# shm.net
KiCad netlist of a schematic drawn in EAGLE
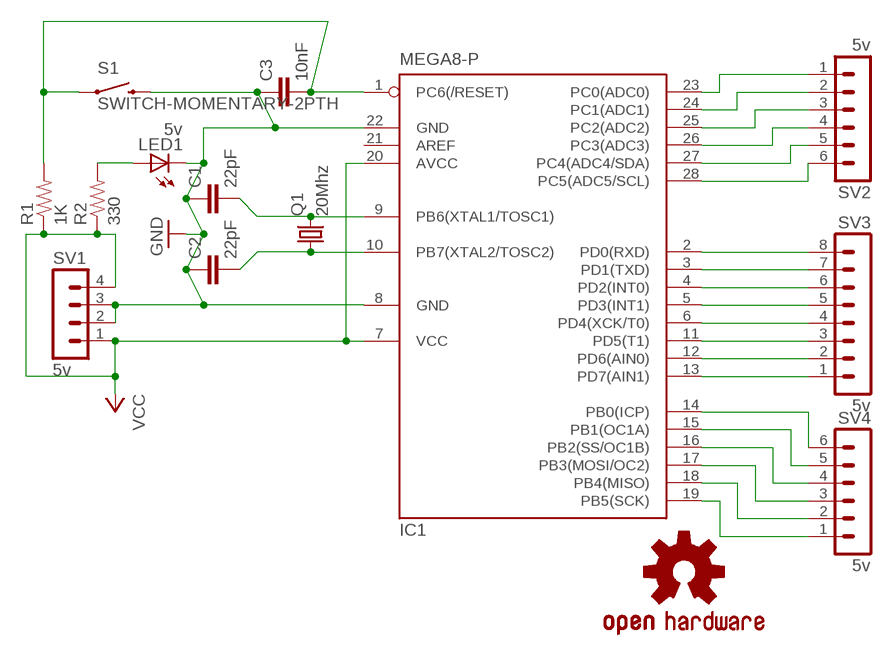
[diagram p0: schematic, sheet 1]

(export (version "E")
  (design (tool "Eeschema 10.0.6"))
  (components
    (comp (ref "C1")
      (value "22pF")
      (footprint "eagle-import:0805")
      (libsource (lib "eagle-import") (part "CAP0805"))
    )
    (comp (ref "C2")
      (value "22pF")
      (footprint "eagle-import:0805")
      (libsource (lib "eagle-import") (part "CAP0805"))
    )
    (comp (ref "C3")
      (value "10nF")
      (footprint "eagle-import:0805")
      (libsource (lib "eagle-import") (part "CAP0805"))
    )
    (comp (ref "IC1")
      (value "MEGA8-P")
      (footprint "eagle-import:DIL28-3")
      (libsource (lib "eagle-import") (part "MEGA8-P"))
    )
    (comp (ref "LED1")
      (value "5v")
      (footprint "eagle-import:CHIPLED_0805")
      (libsource (lib "eagle-import") (part "LEDCHIPLED_0805"))
    )
    (comp (ref "LOGO1")
      (value "OSHW-LOGOL")
      (footprint "eagle-import:OSHW-LOGO-L")
      (libsource (lib "eagle-import") (part "OSHW-LOGOL"))
    )
    (comp (ref "Q1")
      (value "20Mhz")
      (footprint "eagle-import:SM49")
      (libsource (lib "eagle-import") (part "CRYSTALSM49"))
    )
    (comp (ref "R1")
      (value "1K")
      (footprint "eagle-import:0805")
      (libsource (lib "eagle-import") (part "RESISTOR0805-RES"))
    )
    (comp (ref "R2")
      (value "330")
      (footprint "eagle-import:0805")
      (libsource (lib "eagle-import") (part "RESISTOR0805-RES"))
    )
    (comp (ref "S1")
      (value "SWITCH-MOMENTARY-2PTH")
      (footprint "eagle-import:TACTILE-PTH")
      (libsource (lib "eagle-import") (part "SWITCH-MOMENTARY-2PTH"))
    )
    (comp (ref "SV1")
      (value "5v")
      (footprint "eagle-import:MA04-1")
      (libsource (lib "eagle-import") (part "MA04-1"))
    )
    (comp (ref "SV2")
      (value "5v")
      (footprint "eagle-import:MA06-1")
      (libsource (lib "eagle-import") (part "MA06-1"))
    )
    (comp (ref "SV3")
      (value "5v")
      (footprint "eagle-import:MA08-1")
      (libsource (lib "eagle-import") (part "MA08-1"))
    )
    (comp (ref "SV4")
      (value "5v")
      (footprint "eagle-import:MA06-1")
      (libsource (lib "eagle-import") (part "MA06-1"))
    )
  )
  (nets
    (net (code "1") (name "GND") (class "Default")
      (node (ref "C1") (pin "1") (pinfunction "1_1") (pintype "passive"))
      (node (ref "C2") (pin "1") (pinfunction "1_1") (pintype "passive"))
      (node (ref "C3") (pin "1") (pinfunction "1_1") (pintype "passive"))
      (node (ref "IC1") (pin "22") (pinfunction "GND_22") (pintype "power_in"))
      (node (ref "IC1") (pin "8") (pinfunction "GND_8") (pintype "power_in"))
      (node (ref "LED1") (pin "C") (pinfunction "C_C") (pintype "passive"))
      (node (ref "S1") (pin "3") (pinfunction "2_3") (pintype "passive"))
      (node (ref "SV1") (pin "2") (pinfunction "2_2") (pintype "passive"))
      (node (ref "SV1") (pin "3") (pinfunction "3_3") (pintype "passive"))
    )
    (net (code "2") (name "Net-(IC1-PB0(ICP))") (class "Default")
      (node (ref "IC1") (pin "14") (pinfunction "PB0(ICP)_14") (pintype "bidirectional"))
      (node (ref "SV4") (pin "6") (pinfunction "6_6") (pintype "passive"))
    )
    (net (code "3") (name "Net-(IC1-PB1(OC1A))") (class "Default")
      (node (ref "IC1") (pin "15") (pinfunction "PB1(OC1A)_15") (pintype "bidirectional"))
      (node (ref "SV4") (pin "5") (pinfunction "5_5") (pintype "passive"))
    )
    (net (code "4") (name "Net-(IC1-PB2(SS{slash}OC1B))") (class "Default")
      (node (ref "IC1") (pin "16") (pinfunction "PB2(SS/OC1B)_16") (pintype "bidirectional"))
      (node (ref "SV4") (pin "4") (pinfunction "4_4") (pintype "passive"))
    )
    (net (code "5") (name "Net-(IC1-PB3(MOSI{slash}OC2))") (class "Default")
      (node (ref "IC1") (pin "17") (pinfunction "PB3(MOSI/OC2)_17") (pintype "bidirectional"))
      (node (ref "SV4") (pin "3") (pinfunction "3_3") (pintype "passive"))
    )
    (net (code "6") (name "Net-(IC1-PB4(MISO))") (class "Default")
      (node (ref "IC1") (pin "18") (pinfunction "PB4(MISO)_18") (pintype "bidirectional"))
      (node (ref "SV4") (pin "2") (pinfunction "2_2") (pintype "passive"))
    )
    (net (code "7") (name "Net-(IC1-PB5(SCK))") (class "Default")
      (node (ref "IC1") (pin "19") (pinfunction "PB5(SCK)_19") (pintype "bidirectional"))
      (node (ref "SV4") (pin "1") (pinfunction "1_1") (pintype "passive"))
    )
    (net (code "8") (name "Net-(IC1-PB6(XTAL1{slash}TOSC1))") (class "Default")
      (node (ref "C1") (pin "2") (pinfunction "2_2") (pintype "passive"))
      (node (ref "IC1") (pin "9") (pinfunction "PB6(XTAL1/TOSC1)_9") (pintype "bidirectional"))
      (node (ref "Q1") (pin "2") (pinfunction "2_2") (pintype "passive"))
    )
    (net (code "9") (name "Net-(IC1-PB7(XTAL2{slash}TOSC2))") (class "Default")
      (node (ref "C2") (pin "2") (pinfunction "2_2") (pintype "passive"))
      (node (ref "IC1") (pin "10") (pinfunction "PB7(XTAL2/TOSC2)_10") (pintype "bidirectional"))
      (node (ref "Q1") (pin "1") (pinfunction "1_1") (pintype "passive"))
    )
    (net (code "10") (name "Net-(IC1-PC0(ADC0))") (class "Default")
      (node (ref "IC1") (pin "23") (pinfunction "PC0(ADC0)_23") (pintype "bidirectional"))
      (node (ref "SV2") (pin "1") (pinfunction "1_1") (pintype "passive"))
    )
    (net (code "11") (name "Net-(IC1-PC1(ADC1))") (class "Default")
      (node (ref "IC1") (pin "24") (pinfunction "PC1(ADC1)_24") (pintype "bidirectional"))
      (node (ref "SV2") (pin "2") (pinfunction "2_2") (pintype "passive"))
    )
    (net (code "12") (name "Net-(IC1-PC2(ADC2))") (class "Default")
      (node (ref "IC1") (pin "25") (pinfunction "PC2(ADC2)_25") (pintype "bidirectional"))
      (node (ref "SV2") (pin "3") (pinfunction "3_3") (pintype "passive"))
    )
    (net (code "13") (name "Net-(IC1-PC3(ADC3))") (class "Default")
      (node (ref "IC1") (pin "26") (pinfunction "PC3(ADC3)_26") (pintype "bidirectional"))
      (node (ref "SV2") (pin "4") (pinfunction "4_4") (pintype "passive"))
    )
    (net (code "14") (name "Net-(IC1-PC4(ADC4{slash}SDA))") (class "Default")
      (node (ref "IC1") (pin "27") (pinfunction "PC4(ADC4/SDA)_27") (pintype "bidirectional"))
      (node (ref "SV2") (pin "5") (pinfunction "5_5") (pintype "passive"))
    )
    (net (code "15") (name "Net-(IC1-PC5(ADC5{slash}SCL))") (class "Default")
      (node (ref "IC1") (pin "28") (pinfunction "PC5(ADC5/SCL)_28") (pintype "bidirectional"))
      (node (ref "SV2") (pin "6") (pinfunction "6_6") (pintype "passive"))
    )
    (net (code "16") (name "Net-(IC1-PC6({slash}RESET))") (class "Default")
      (node (ref "C3") (pin "2") (pinfunction "2_2") (pintype "passive"))
      (node (ref "IC1") (pin "1") (pinfunction "PC6(/RESET)_1") (pintype "bidirectional"))
      (node (ref "R1") (pin "2") (pinfunction "2_2") (pintype "passive"))
      (node (ref "S1") (pin "1") (pinfunction "1_1") (pintype "passive"))
    )
    (net (code "17") (name "Net-(IC1-PD0(RXD))") (class "Default")
      (node (ref "IC1") (pin "2") (pinfunction "PD0(RXD)_2") (pintype "bidirectional"))
      (node (ref "SV3") (pin "8") (pinfunction "8_8") (pintype "passive"))
    )
    (net (code "18") (name "Net-(IC1-PD1(TXD))") (class "Default")
      (node (ref "IC1") (pin "3") (pinfunction "PD1(TXD)_3") (pintype "bidirectional"))
      (node (ref "SV3") (pin "7") (pinfunction "7_7") (pintype "passive"))
    )
    (net (code "19") (name "Net-(IC1-PD2(INT0))") (class "Default")
      (node (ref "IC1") (pin "4") (pinfunction "PD2(INT0)_4") (pintype "bidirectional"))
      (node (ref "SV3") (pin "6") (pinfunction "6_6") (pintype "passive"))
    )
    (net (code "20") (name "Net-(IC1-PD3(INT1))") (class "Default")
      (node (ref "IC1") (pin "5") (pinfunction "PD3(INT1)_5") (pintype "bidirectional"))
      (node (ref "SV3") (pin "5") (pinfunction "5_5") (pintype "passive"))
    )
    (net (code "21") (name "Net-(IC1-PD4(XCK{slash}T0))") (class "Default")
      (node (ref "IC1") (pin "6") (pinfunction "PD4(XCK/T0)_6") (pintype "bidirectional"))
      (node (ref "SV3") (pin "4") (pinfunction "4_4") (pintype "passive"))
    )
    (net (code "22") (name "Net-(IC1-PD5(T1))") (class "Default")
      (node (ref "IC1") (pin "11") (pinfunction "PD5(T1)_11") (pintype "bidirectional"))
      (node (ref "SV3") (pin "3") (pinfunction "3_3") (pintype "passive"))
    )
    (net (code "23") (name "Net-(IC1-PD6(AIN0))") (class "Default")
      (node (ref "IC1") (pin "12") (pinfunction "PD6(AIN0)_12") (pintype "bidirectional"))
      (node (ref "SV3") (pin "2") (pinfunction "2_2") (pintype "passive"))
    )
    (net (code "24") (name "Net-(IC1-PD7(AIN1))") (class "Default")
      (node (ref "IC1") (pin "13") (pinfunction "PD7(AIN1)_13") (pintype "bidirectional"))
      (node (ref "SV3") (pin "1") (pinfunction "1_1") (pintype "passive"))
    )
    (net (code "25") (name "Net-(LED1-PadA)") (class "Default")
      (node (ref "LED1") (pin "A") (pinfunction "A_A") (pintype "passive"))
      (node (ref "R2") (pin "2") (pinfunction "2_2") (pintype "passive"))
    )
    (net (code "26") (name "VCC") (class "Default")
      (node (ref "IC1") (pin "20") (pinfunction "AVCC_20") (pintype "power_in"))
      (node (ref "IC1") (pin "7") (pinfunction "VCC_7") (pintype "power_in"))
      (node (ref "R1") (pin "1") (pinfunction "1_1") (pintype "passive"))
      (node (ref "R2") (pin "1") (pinfunction "1_1") (pintype "passive"))
      (node (ref "SV1") (pin "1") (pinfunction "1_1") (pintype "passive"))
      (node (ref "SV1") (pin "4") (pinfunction "4_4") (pintype "passive"))
    )
    (net (code "27") (name "unconnected-(IC1-AREF-Pad21)") (class "Default")
      (node (ref "IC1") (pin "21") (pinfunction "AREF_21") (pintype "passive"))
    )
  )
)
